# Fuente_v1.net
KiCad netlist of a schematic drawn in EAGLE
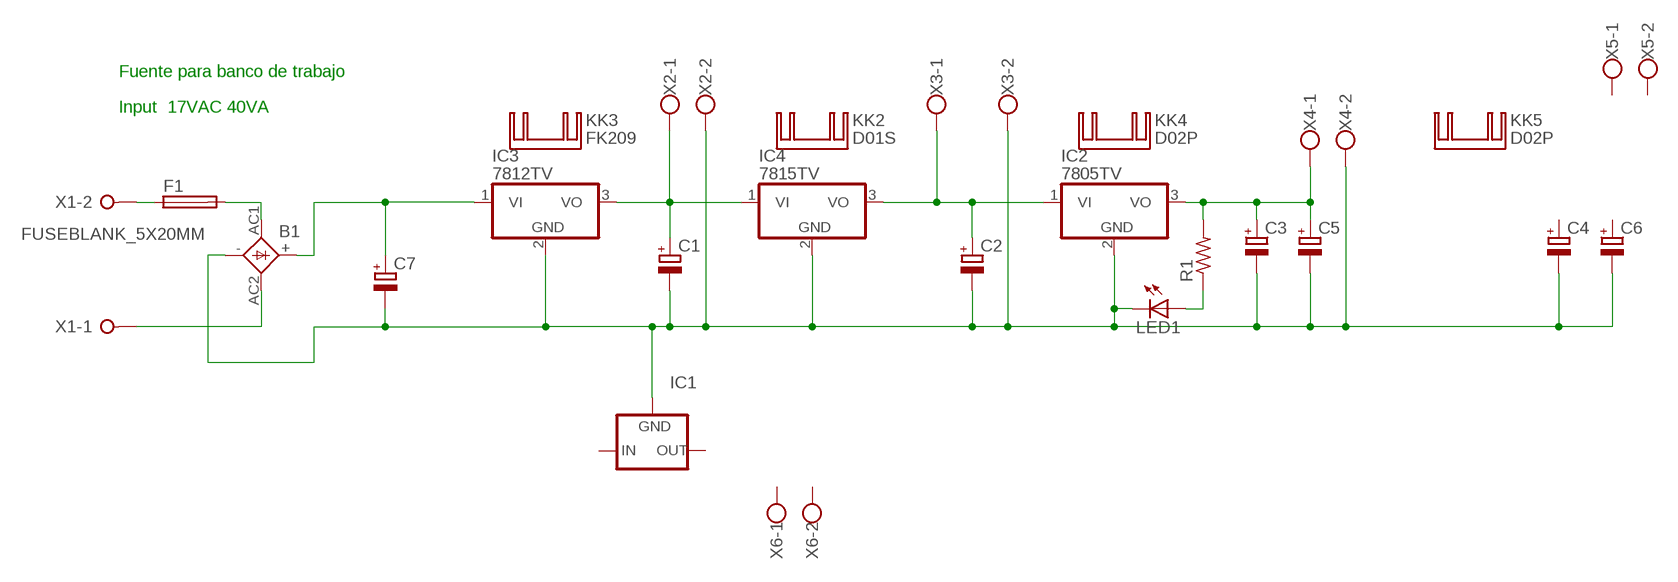
[diagram p0: schematic, sheet 1]

(export (version "E")
  (design (tool "Eeschema 10.0.6"))
  (components
    (comp (ref "B1")
      (value "S51")
      (footprint "eagle-import:S51")
      (libsource (lib "eagle-import") (part "S51"))
    )
    (comp (ref "C1")
      (value "CPOL-EUE2.5-7")
      (footprint "eagle-import:E2,5-7")
      (libsource (lib "eagle-import") (part "CPOL-EUE2.5-7"))
    )
    (comp (ref "C2")
      (value "CPOL-EUE2.5-7")
      (footprint "eagle-import:E2,5-7")
      (libsource (lib "eagle-import") (part "CPOL-EUE2.5-7"))
    )
    (comp (ref "C3")
      (value "CPOL-EUE2.5-7")
      (footprint "eagle-import:E2,5-7")
      (libsource (lib "eagle-import") (part "CPOL-EUE2.5-7"))
    )
    (comp (ref "C4")
      (value "CPOL-EUE2.5-6")
      (footprint "eagle-import:E2,5-6")
      (libsource (lib "eagle-import") (part "CPOL-EUE2.5-6"))
    )
    (comp (ref "C5")
      (value "CPOL-EUE2.5-6")
      (footprint "eagle-import:E2,5-6")
      (libsource (lib "eagle-import") (part "CPOL-EUE2.5-6"))
    )
    (comp (ref "C6")
      (value "CPOL-EUE2.5-6")
      (footprint "eagle-import:E2,5-6")
      (libsource (lib "eagle-import") (part "CPOL-EUE2.5-6"))
    )
    (comp (ref "C7")
      (value "CPOL-EUE2.5-7")
      (footprint "eagle-import:E2,5-7")
      (libsource (lib "eagle-import") (part "CPOL-EUE2.5-7"))
    )
    (comp (ref "F1")
      (value "FUSEBLANK_5X20MM")
      (footprint "eagle-import:FUSE_HOLDER_5X20MM")
      (libsource (lib "eagle-import") (part "FUSEBLANK_5X20MM"))
    )
    (comp (ref "IC1")
      (value "79XX-TO3")
      (footprint "eagle-import:TO3-79")
      (libsource (lib "eagle-import") (part "79XX-TO3"))
    )
    (comp (ref "IC2")
      (value "7805TV")
      (footprint "eagle-import:TO220V")
      (libsource (lib "eagle-import") (part "78TV05"))
    )
    (comp (ref "IC3")
      (value "7812TV")
      (footprint "eagle-import:TO220V")
      (libsource (lib "eagle-import") (part "78TV12"))
    )
    (comp (ref "IC4")
      (value "7815TV")
      (footprint "eagle-import:TO220V")
      (libsource (lib "eagle-import") (part "78TV15"))
    )
    (comp (ref "KK2")
      (value "D01S")
      (footprint "eagle-import:D01S")
      (libsource (lib "eagle-import") (part "D01S"))
    )
    (comp (ref "KK3")
      (value "FK209")
      (footprint "eagle-import:FK209")
      (libsource (lib "eagle-import") (part "FK209"))
    )
    (comp (ref "KK4")
      (value "D02P")
      (footprint "eagle-import:D02PA")
      (libsource (lib "eagle-import") (part "D02P"))
    )
    (comp (ref "KK5")
      (value "D02P")
      (footprint "eagle-import:D02PA")
      (libsource (lib "eagle-import") (part "D02P"))
    )
    (comp (ref "LED1")
      (value "LED5MM")
      (footprint "eagle-import:LED5MM")
      (libsource (lib "eagle-import") (part "LED5MM"))
    )
    (comp (ref "R1")
      (value "R-US_0204/7")
      (footprint "eagle-import:0204_7")
      (libsource (lib "eagle-import") (part "R-US_0204/7"))
    )
    (comp (ref "X1")
      (value "W237-02P")
      (footprint "eagle-import:W237-132")
      (libsource (lib "eagle-import") (part "W237-02P"))
    )
    (comp (ref "X2")
      (value "W237-102")
      (footprint "eagle-import:W237-102")
      (fields (field (name "MPN") "237-102"))
      (libsource (lib "eagle-import") (part "W237-102"))
    )
    (comp (ref "X3")
      (value "W237-102")
      (footprint "eagle-import:W237-102")
      (fields (field (name "MPN") "237-102"))
      (libsource (lib "eagle-import") (part "W237-102"))
    )
    (comp (ref "X4")
      (value "W237-102")
      (footprint "eagle-import:W237-102")
      (fields (field (name "MPN") "237-102"))
      (libsource (lib "eagle-import") (part "W237-102"))
    )
    (comp (ref "X5")
      (value "W237-102")
      (footprint "eagle-import:W237-102")
      (fields (field (name "MPN") "237-102"))
      (libsource (lib "eagle-import") (part "W237-102"))
    )
    (comp (ref "X6")
      (value "W237-102")
      (footprint "eagle-import:W237-102")
      (fields (field (name "MPN") "237-102"))
      (libsource (lib "eagle-import") (part "W237-102"))
    )
  )
  (nets
    (net (code "1") (name "Net-(B1-PadAC1)") (class "Default")
      (node (ref "B1") (pin "AC1") (pinfunction "AC1_AC1") (pintype "passive"))
      (node (ref "F1") (pin "2") (pinfunction "2_2") (pintype "passive"))
    )
    (net (code "2") (name "Net-(IC1-GND)") (class "Default")
      (node (ref "B1") (pin "-") (pinfunction "-_-") (pintype "passive"))
      (node (ref "C1") (pin "-") (pinfunction "-_-") (pintype "passive"))
      (node (ref "C2") (pin "-") (pinfunction "-_-") (pintype "passive"))
      (node (ref "C3") (pin "-") (pinfunction "-_-") (pintype "passive"))
      (node (ref "C4") (pin "-") (pinfunction "-_-") (pintype "passive"))
      (node (ref "C5") (pin "-") (pinfunction "-_-") (pintype "passive"))
      (node (ref "C6") (pin "-") (pinfunction "-_-") (pintype "passive"))
      (node (ref "C7") (pin "-") (pinfunction "-_-") (pintype "passive"))
      (node (ref "IC1") (pin "2") (pinfunction "GND_2") (pintype "input"))
      (node (ref "IC2") (pin "2") (pinfunction "GND_2") (pintype "passive"))
      (node (ref "IC3") (pin "2") (pinfunction "GND_2") (pintype "passive"))
      (node (ref "IC4") (pin "2") (pinfunction "GND_2") (pintype "passive"))
      (node (ref "LED1") (pin "K") (pinfunction "C_K") (pintype "passive"))
      (node (ref "X2") (pin "2") (pinfunction "KL_2") (pintype "passive"))
      (node (ref "X3") (pin "2") (pinfunction "KL_2") (pintype "passive"))
      (node (ref "X4") (pin "2") (pinfunction "KL_2") (pintype "passive"))
    )
    (net (code "3") (name "Net-(IC2-VI)") (class "Default")
      (node (ref "C2") (pin "+") (pinfunction "+_+") (pintype "passive"))
      (node (ref "IC2") (pin "1") (pinfunction "VI_1") (pintype "input"))
      (node (ref "IC4") (pin "3") (pinfunction "VO_3") (pintype "passive"))
      (node (ref "X3") (pin "1") (pinfunction "KL_1") (pintype "passive"))
    )
    (net (code "4") (name "Net-(IC2-VO)") (class "Default")
      (node (ref "C3") (pin "+") (pinfunction "+_+") (pintype "passive"))
      (node (ref "C5") (pin "+") (pinfunction "+_+") (pintype "passive"))
      (node (ref "IC2") (pin "3") (pinfunction "VO_3") (pintype "passive"))
      (node (ref "R1") (pin "2") (pinfunction "2_2") (pintype "passive"))
      (node (ref "X4") (pin "1") (pinfunction "KL_1") (pintype "passive"))
    )
    (net (code "5") (name "Net-(IC3-VI)") (class "Default")
      (node (ref "B1") (pin "+") (pinfunction "+_+") (pintype "passive"))
      (node (ref "C7") (pin "+") (pinfunction "+_+") (pintype "passive"))
      (node (ref "IC3") (pin "1") (pinfunction "VI_1") (pintype "input"))
    )
    (net (code "6") (name "Net-(IC3-VO)") (class "Default")
      (node (ref "C1") (pin "+") (pinfunction "+_+") (pintype "passive"))
      (node (ref "IC3") (pin "3") (pinfunction "VO_3") (pintype "passive"))
      (node (ref "IC4") (pin "1") (pinfunction "VI_1") (pintype "input"))
      (node (ref "X2") (pin "1") (pinfunction "KL_1") (pintype "passive"))
    )
    (net (code "7") (name "Net-(LED1-PadA)") (class "Default")
      (node (ref "LED1") (pin "A") (pinfunction "A_A") (pintype "passive"))
      (node (ref "R1") (pin "1") (pinfunction "1_1") (pintype "passive"))
    )
    (net (code "8") (name "Net-(X1A-KL)") (class "Default")
      (node (ref "B1") (pin "AC2") (pinfunction "AC2_AC2") (pintype "passive"))
      (node (ref "X1") (pin "1") (pinfunction "KL_1") (pintype "passive"))
    )
    (net (code "9") (name "Net-(X1B-KL)") (class "Default")
      (node (ref "F1") (pin "1") (pinfunction "1_1") (pintype "passive"))
      (node (ref "X1") (pin "2") (pinfunction "KL_2") (pintype "passive"))
    )
    (net (code "10") (name "unconnected-(C4-Pad+)") (class "Default")
      (node (ref "C4") (pin "+") (pinfunction "+_+") (pintype "passive"))
    )
    (net (code "11") (name "unconnected-(C6-Pad+)") (class "Default")
      (node (ref "C6") (pin "+") (pinfunction "+_+") (pintype "passive"))
    )
    (net (code "12") (name "unconnected-(IC1-IN-Pad3)") (class "Default")
      (node (ref "IC1") (pin "3") (pinfunction "IN_3") (pintype "input"))
    )
    (net (code "13") (name "unconnected-(IC1-OUT-Pad1)") (class "Default")
      (node (ref "IC1") (pin "1") (pinfunction "OUT_1") (pintype "passive"))
    )
    (net (code "14") (name "unconnected-(X5A-KL-Pad1)") (class "Default")
      (node (ref "X5") (pin "1") (pinfunction "KL_1") (pintype "passive"))
    )
    (net (code "15") (name "unconnected-(X5B-KL-Pad2)") (class "Default")
      (node (ref "X5") (pin "2") (pinfunction "KL_2") (pintype "passive"))
    )
    (net (code "16") (name "unconnected-(X6A-KL-Pad1)") (class "Default")
      (node (ref "X6") (pin "1") (pinfunction "KL_1") (pintype "passive"))
    )
    (net (code "17") (name "unconnected-(X6B-KL-Pad2)") (class "Default")
      (node (ref "X6") (pin "2") (pinfunction "KL_2") (pintype "passive"))
    )
  )
)
